# SUNNYMultiAnalyzor.net
KiCad netlist of a schematic drawn in Altium Designer
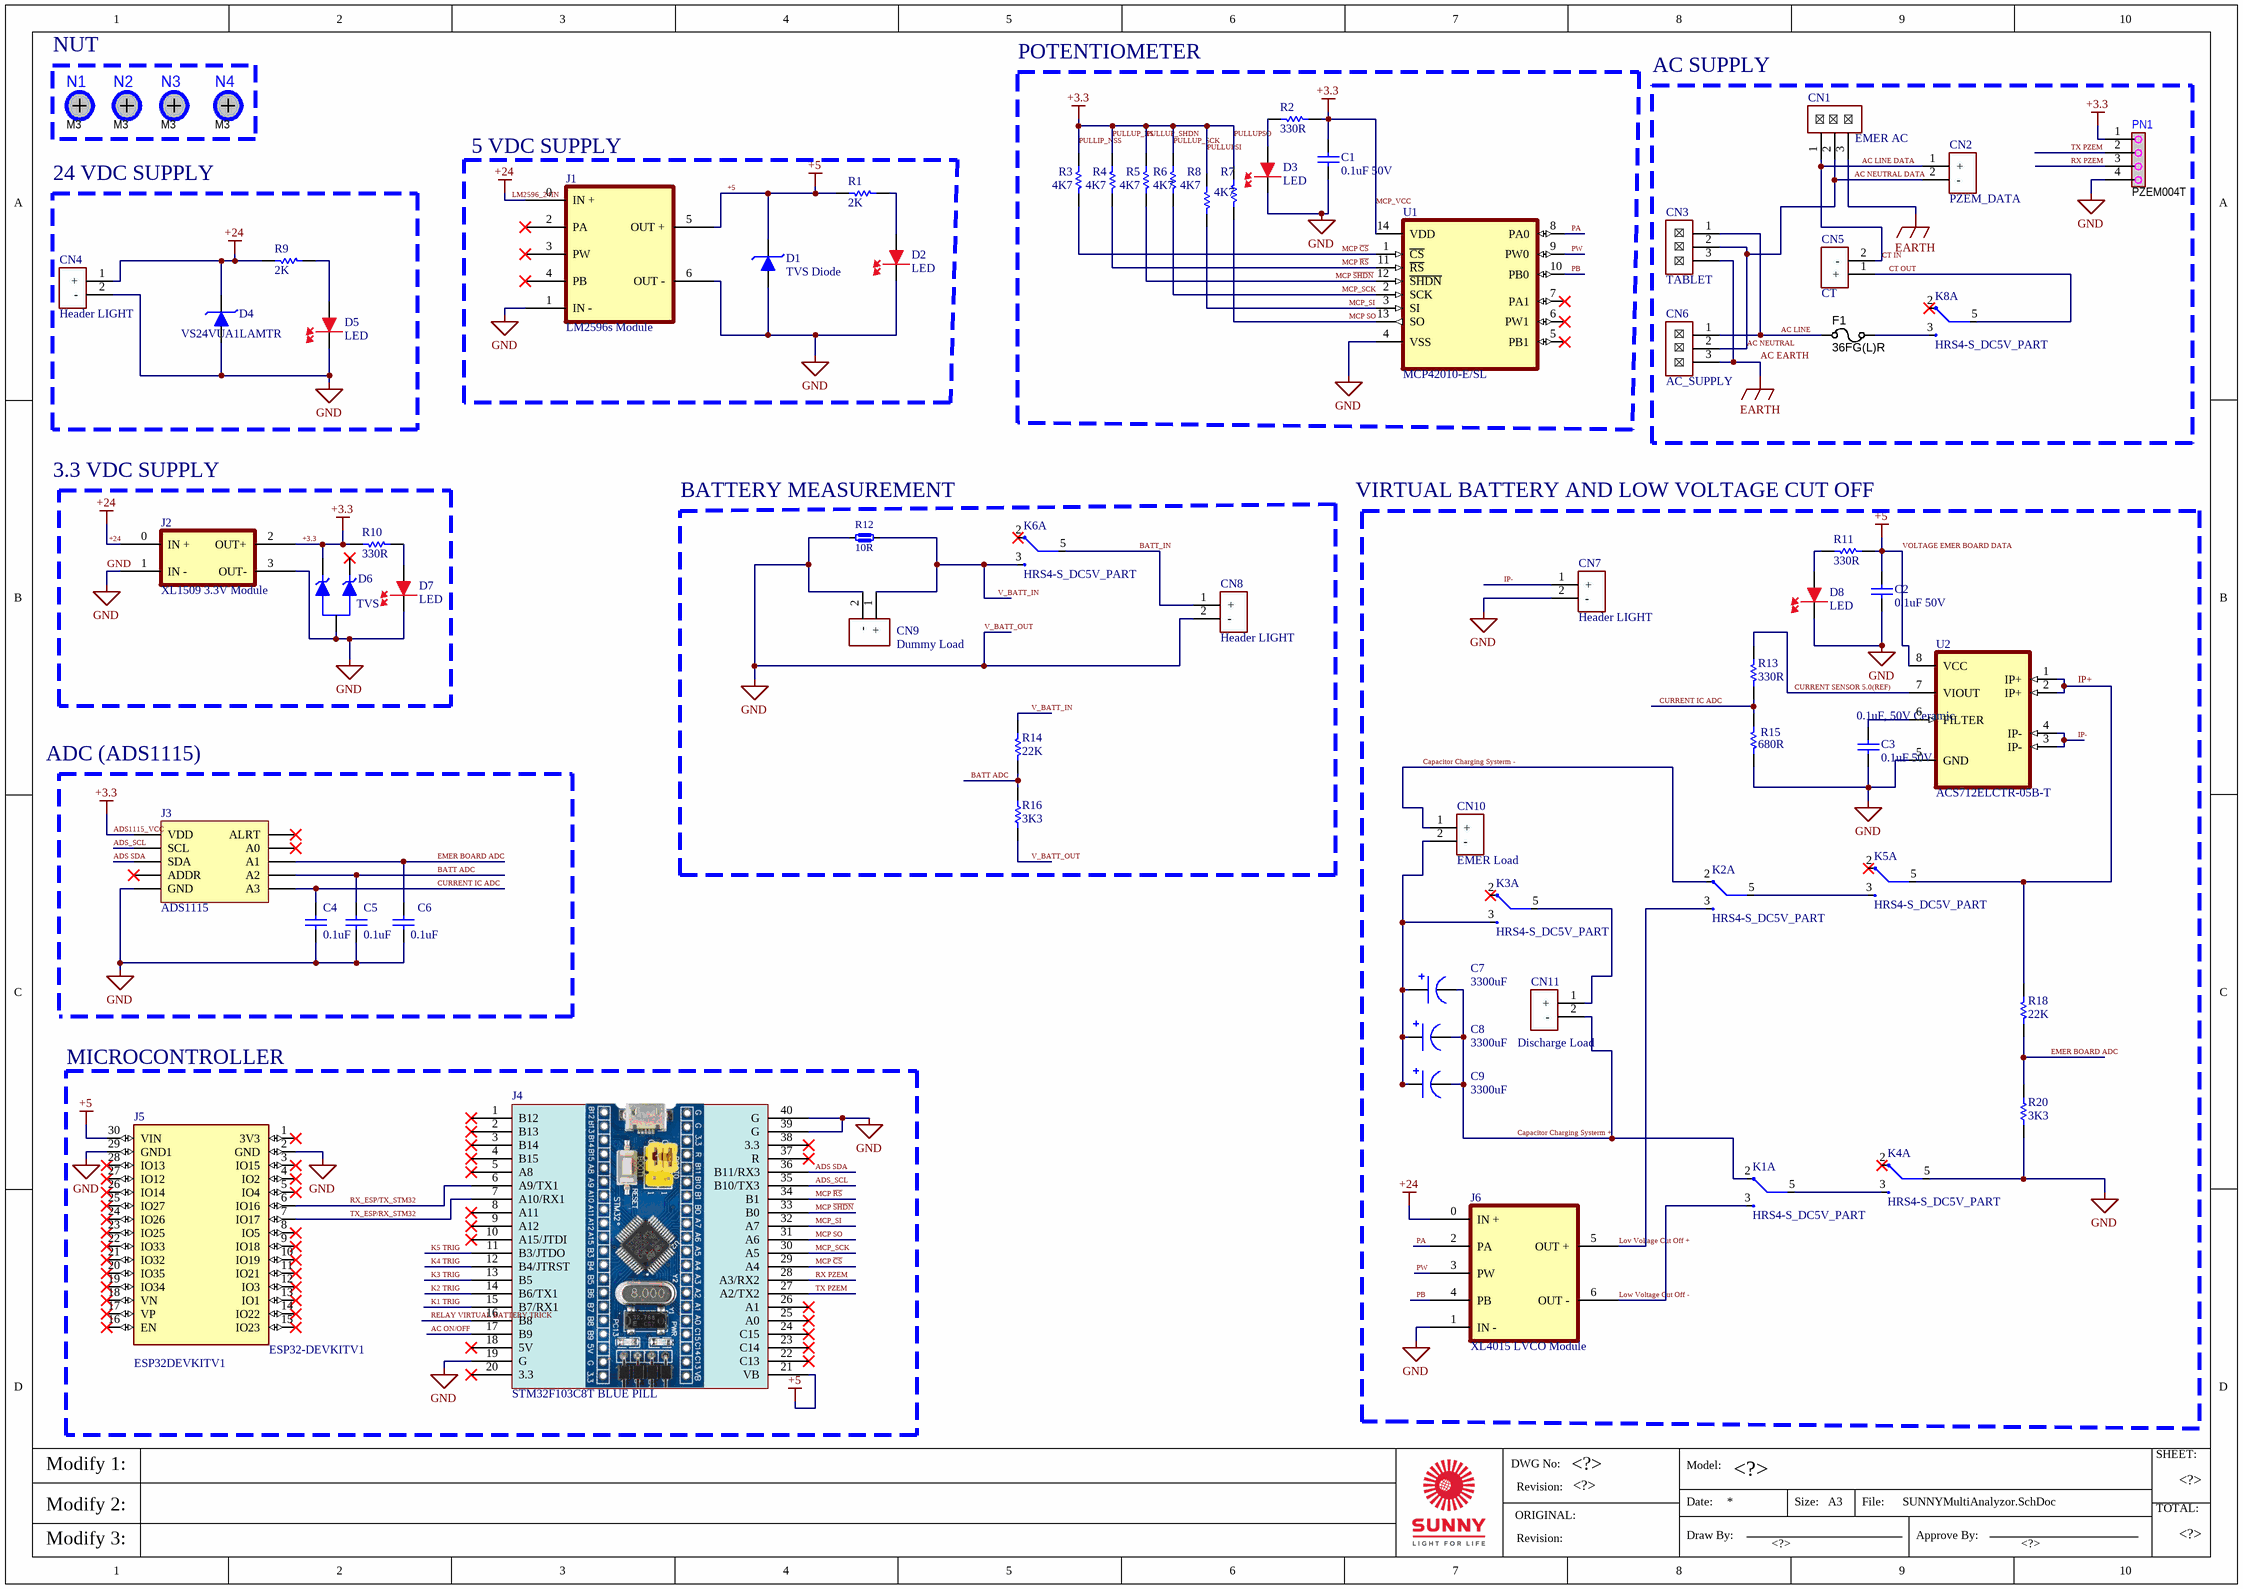
[diagram p0: SUNNYMultiAnalyzor.SchDoc]

(export (version "E")
  (design (tool "Eeschema 10.0.6"))
  (components
    (comp (ref "C1")
      (value "0.1uF 50V")
      (footprint "CAPC2012X135N")
      (description "Capacitor SMD Ceramic Chip Cap 0.1uF 50V (0805) (AVX)")
      (fields (field (name "CREATED BY") "Zion Blue") (field (name "PUBLISHER") "Cynetik Group"))
      (libsource (lib "Control INV-V21") (part "Capacitor SMD Ceramic Chip Cap 0.1uF 50V (0805) (AVX)"))
    )
    (comp (ref "C2")
      (value "0.1uF 50V")
      (footprint "CAPC2012X135N")
      (description "Capacitor SMD Ceramic Chip Cap 0.1uF 50V (0805) (AVX)")
      (fields (field (name "CREATED BY") "Zion Blue") (field (name "PUBLISHER") "Cynetik Group"))
      (libsource (lib "Control INV-V21") (part "Capacitor SMD Ceramic Chip Cap 0.1uF 50V (0805) (AVX)"))
    )
    (comp (ref "C3")
      (value "0.1uF 50V")
      (footprint "CAPC2012X135N")
      (description "Capacitor SMD Ceramic Chip Cap 0.1uF 50V (0805) (AVX)")
      (fields
        (field (name "ALTIUM_VALUE") "0.1uF, 50V Ceramic")
        (field (name "CREATED BY") "Zion Blue")
        (field (name "PUBLISHER") "Cynetik Group")
      )
      (libsource (lib "Control INV-V21") (part "Capacitor SMD Ceramic Chip Cap 0.1uF 50V (0805) (AVX)"))
    )
    (comp (ref "C4")
      (value "0.1uF")
      (footprint "CAPC2012X135N")
      (description "Capacitor SMD Ceramic Chip Cap 0.1uF 50V (0805) (AVX)")
      (fields (field (name "CREATED BY") "Zion Blue") (field (name "PUBLISHER") "Cynetik Group"))
      (libsource (lib "Control INV-V21") (part "Capacitor SMD Ceramic Chip Cap 0.1uF 50V (0805) (AVX)"))
    )
    (comp (ref "C5")
      (value "0.1uF")
      (footprint "CAPC2012X135N")
      (description "Capacitor SMD Ceramic Chip Cap 0.1uF 50V (0805) (AVX)")
      (fields (field (name "CREATED BY") "Zion Blue") (field (name "PUBLISHER") "Cynetik Group"))
      (libsource (lib "Control INV-V21") (part "Capacitor SMD Ceramic Chip Cap 0.1uF 50V (0805) (AVX)"))
    )
    (comp (ref "C6")
      (value "0.1uF")
      (footprint "CAPC2012X135N")
      (description "Capacitor SMD Ceramic Chip Cap 0.1uF 50V (0805) (AVX)")
      (fields (field (name "CREATED BY") "Zion Blue") (field (name "PUBLISHER") "Cynetik Group"))
      (libsource (lib "Control INV-V21") (part "Capacitor SMD Ceramic Chip Cap 0.1uF 50V (0805) (AVX)"))
    )
    (comp (ref "C7")
      (value "3300uF")
      (footprint "CAP3300")
      (description "3300 uF / 50 Vdc")
      (libsource (lib "PCB_Project_1") (part "Electrolytic Capacitor"))
    )
    (comp (ref "C8")
      (value "3300uF")
      (footprint "CAP3300")
      (description "3300 uF / 50 Vdc")
      (libsource (lib "PCB_Project_1") (part "Electrolytic Capacitor"))
    )
    (comp (ref "C9")
      (value "3300uF")
      (footprint "CAP3300")
      (description "3300 uF / 50 Vdc")
      (libsource (lib "PCB_Project_1") (part "Electrolytic Capacitor"))
    )
    (comp (ref "CN1")
      (value "EMER AC")
      (footprint "CON 3P 3.8mm")
      (description "Connector 3.9mm. 3PINS WAFER STRAIGHT PIN (MALE)")
      (fields (field (name "MPN") "112002ST/RH") (field (name "MANUFACTURER") "GTK"))
      (libsource (lib "MCU POWER BOARD") (part "Con 112002ST/RH 3.96mm 2P V-PLUG_1"))
    )
    (comp (ref "CN2")
      (value "PZEM_DATA")
      (footprint "Header 2 pin molex")
      (description "Connector 3.96MM 02 PIN WAFER STRAIGHTPIN (MALE)")
      (libsource (lib "MCU POWER BOARD") (part "Header LIGHT"))
    )
    (comp (ref "CN3")
      (value "TABLET")
      (footprint "CON 3P 3.8mm")
      (description "Connector 3.9mm. 3PINS WAFER STRAIGHT PIN (MALE)")
      (fields (field (name "MPN") "112002ST/RH") (field (name "MANUFACTURER") "GTK"))
      (libsource (lib "") (part "Con 112002ST/RH 3.96mm 2P V-PLUG_1_1"))
    )
    (comp (ref "CN4")
      (value "Header LIGHT")
      (footprint "HEADER 2 PIN MOLEX POLE")
      (description "Connector 3.96MM 02 PIN WAFER STRAIGHTPIN (MALE)")
      (libsource (lib "") (part "CON Header LIGHT Pole_1"))
    )
    (comp (ref "CN5")
      (value "CT")
      (footprint "Header 2 pin molex")
      (description "Connector 3.96MM 02 PIN WAFER STRAIGHTPIN (MALE)")
      (libsource (lib "") (part "Header LIGHT_2"))
    )
    (comp (ref "CN6")
      (value "AC_SUPPLY")
      (footprint "CON 3P 3.8mm")
      (description "Connector 3.9mm. 3PINS WAFER STRAIGHT PIN (MALE)")
      (fields (field (name "MPN") "112002ST/RH") (field (name "MANUFACTURER") "GTK"))
      (libsource (lib "") (part "Con 112002ST/RH 3.96mm 2P V-PLUG_1_1"))
    )
    (comp (ref "CN7")
      (value "Header LIGHT")
      (footprint "HEADER 2 PIN MOLEX POLE")
      (description "Connector 3.96MM 02 PIN WAFER STRAIGHTPIN (MALE)")
      (libsource (lib "ESP32+ATMEL") (part "CON Header LIGHT Pole"))
    )
    (comp (ref "CN8")
      (value "Header LIGHT")
      (footprint "HEADER 2 PIN MOLEX POLE")
      (description "Connector 3.96MM 02 PIN WAFER STRAIGHTPIN (MALE)")
      (libsource (lib "ESP32+ATMEL") (part "CON Header LIGHT Pole"))
    )
    (comp (ref "CN9")
      (value "Dummy Load")
      (footprint "Header 2 pin molex")
      (description "Connector 3.96MM 02 PIN WAFER STRAIGHTPIN (MALE)")
      (libsource (lib "") (part "Header LIGHT_1"))
    )
    (comp (ref "CN10")
      (value "EMER Load")
      (footprint "Header 2 pin molex")
      (description "Connector 3.96MM 02 PIN WAFER STRAIGHTPIN (MALE)")
      (libsource (lib "MCU POWER BOARD") (part "Header LIGHT"))
    )
    (comp (ref "CN11")
      (value "Discharge Load")
      (footprint "Header 2 pin molex")
      (description "Connector 3.96MM 02 PIN WAFER STRAIGHTPIN (MALE)")
      (libsource (lib "") (part "Header LIGHT_1"))
    )
    (comp (ref "D1")
      (value "TVS Diode")
      (footprint "SOD-128")
      (fields (field (name "PUBLISHER") "Altium Limited"))
      (libsource (lib "PCB_Project_1") (part "TVS Diode VS6V0UA1LAMTR"))
    )
    (comp (ref "D2")
      (value "LED")
      (footprint "0805 LED")
      (description "LED SMD  mcd,Red Color Red Diffused Lens")
      (libsource (lib "PCB_Project_1") (part "LED RED (SMD)"))
    )
    (comp (ref "D3")
      (value "LED")
      (footprint "0805 LED")
      (description "LED SMD  mcd,Red Color Red Diffused Lens")
      (libsource (lib "PCB_Project_1") (part "LED RED (SMD)"))
    )
    (comp (ref "D4")
      (value "VS24VUA1LAMTR")
      (footprint "SOD-128")
      (fields (field (name "PUBLISHER") "Altium Limited"))
      (libsource (lib "PCB_Project_1") (part "TVS Diode VS24VUA1LAMTR"))
    )
    (comp (ref "D5")
      (value "LED")
      (footprint "0805 LED")
      (description "LED SMD  mcd,Red Color Red Diffused Lens")
      (libsource (lib "PCB_Project_1") (part "LED RED (SMD)"))
    )
    (comp (ref "D6")
      (value "TVS")
      (footprint "SOT95P237X111-3N")
      (description "46V Clamp 870mA Ipp Tvs Diode Surface Mount SOT-23-3 (TO-236)")
      (fields (field (name "MP") "MMBZ6V8ALT1G"))
      (libsource (lib "PCB_Project_1") (part "TVS Diode MMBZ6V8ALT1G"))
    )
    (comp (ref "D7")
      (value "LED")
      (footprint "0805 LED")
      (description "LED SMD  mcd,Red Color Red Diffused Lens")
      (libsource (lib "PCB_Project_1") (part "LED RED (SMD)"))
    )
    (comp (ref "D8")
      (value "LED")
      (footprint "0805 LED")
      (description "LED SMD  mcd,Red Color Red Diffused Lens")
      (libsource (lib "PCB_Project_1") (part "LED RED (SMD)"))
    )
    (comp (ref "F1")
      (value "36FG(L)R")
      (footprint "Micro Fuse - L14mm")
      (description "Fuse Microfuse, 1A/250Vac, Fast Acting (Normal Blow) P/N : 36FG(L)R (SLEEK)")
      (fields (field (name "MANUFACTURER") "SLEEK") (field (name "PUBLISHER") "Cynetik Group"))
      (libsource (lib "MCU POWER BOARD") (part "Fuse 36FG(L)R 1A On pcb"))
    )
    (comp (ref "J1")
      (value "LM2596s Module")
      (footprint "LM2596s MODULE")
      (description "LM2596s Module step down converter")
      (libsource (lib "PCB_Project_1") (part "LM2596s Module 5A"))
    )
    (comp (ref "J2")
      (value "XL1509 3.3V Module")
      (footprint "XL1509 MODULE")
      (description "XL1509 Module step down converter")
      (libsource (lib "PCB_Project_1") (part "XL1509 Module"))
    )
    (comp (ref "J3")
      (value "ADS1115")
      (footprint "BNO080")
      (description "ADC Sensor")
      (fields (field (name "PUBLISHER") "Altium Limited"))
      (libsource (lib "SchlibBruno") (part "ADS1115"))
    )
    (comp (ref "J4")
      (value "STM32F103C8T BLUE PILL")
      (footprint "STM32F103 BLUE PILL")
      (description "STM32F103C8T BULE PILL")
      (libsource (lib "PCB_Project_1") (part "STM32 BULE PILL"))
    )
    (comp (ref "J5")
      (value "ESP32DEVKITV1")
      (footprint "ESP32-DEVKITV1_3D")
      (fields (field (name "MF") "Do it") (field (name "MP") "ESP32 DEVKIT V1"))
      (libsource (lib "SchlibBruno") (part "ESP32DEVKITV1"))
    )
    (comp (ref "J6")
      (value "XL4015 LVCO Module")
      (footprint "XL4015 Module")
      (description "XL4015 Module step down converter for Low Voltage Cut Off Check(LVCO)")
      (libsource (lib "PCB_Project_1") (part "XL4015 Module 5A"))
    )
    (comp (ref "K1")
      (value "HRS4-S_DC5V_PART")
      (footprint "SamacSys:HRS4SDC5V")
      (description "Relay or Contactor")
      (fields (field (name "MANUFACTURER_PART_NUMBER") "HRS4-S DC5V"))
      (libsource (lib "SamacSys") (part "HRS4-S_DC5V_PART"))
    )
    (comp (ref "K2")
      (value "HRS4-S_DC5V_PART")
      (footprint "SamacSys:HRS4SDC5V")
      (description "Relay or Contactor")
      (fields (field (name "MANUFACTURER_PART_NUMBER") "HRS4-S DC5V"))
      (libsource (lib "SamacSys") (part "HRS4-S_DC5V_PART"))
    )
    (comp (ref "K3")
      (value "HRS4-S_DC5V_PART")
      (footprint "SamacSys:HRS4SDC5V")
      (description "Relay or Contactor")
      (fields (field (name "MANUFACTURER_PART_NUMBER") "HRS4-S DC5V"))
      (libsource (lib "SamacSys") (part "HRS4-S_DC5V_PART"))
    )
    (comp (ref "K4")
      (value "HRS4-S_DC5V_PART")
      (footprint "SamacSys:HRS4SDC5V")
      (description "Relay or Contactor")
      (fields (field (name "MANUFACTURER_PART_NUMBER") "HRS4-S DC5V"))
      (libsource (lib "SamacSys") (part "HRS4-S_DC5V_PART"))
    )
    (comp (ref "K5")
      (value "HRS4-S_DC5V_PART")
      (footprint "SamacSys:HRS4SDC5V")
      (description "Relay or Contactor")
      (fields (field (name "MANUFACTURER_PART_NUMBER") "HRS4-S DC5V"))
      (libsource (lib "SamacSys") (part "HRS4-S_DC5V_PART"))
    )
    (comp (ref "K6")
      (value "HRS4-S_DC5V_PART")
      (footprint "SamacSys:HRS4SDC5V")
      (description "Relay or Contactor")
      (fields (field (name "MANUFACTURER_PART_NUMBER") "HRS4-S DC5V"))
      (libsource (lib "SamacSys") (part "HRS4-S_DC5V_PART"))
    )
    (comp (ref "K8")
      (value "HRS4-S_DC5V_PART")
      (footprint "SamacSys:HRS4SDC5V")
      (description "Relay or Contactor")
      (fields (field (name "MANUFACTURER_PART_NUMBER") "HRS4-S DC5V"))
      (libsource (lib "SamacSys") (part "HRS4-S_DC5V_PART"))
    )
    (comp (ref "N1")
      (value "M3")
      (footprint "M3 hole")
      (description "น็อต JT หัวร่ม สกรูมิลสี่แฉก M3x6")
      (libsource (lib "Control INV-V21") (part "M3 hole"))
    )
    (comp (ref "N2")
      (value "M3")
      (footprint "M3 hole")
      (description "น็อต JT หัวร่ม สกรูมิลสี่แฉก M3x6")
      (libsource (lib "Control INV-V21") (part "M3 hole"))
    )
    (comp (ref "N3")
      (value "M3")
      (footprint "M3 hole")
      (description "น็อต JT หัวร่ม สกรูมิลสี่แฉก M3x6")
      (libsource (lib "Control INV-V21") (part "M3 hole"))
    )
    (comp (ref "N4")
      (value "M3")
      (footprint "M3 hole")
      (description "น็อต JT หัวร่ม สกรูมิลสี่แฉก M3x6")
      (libsource (lib "Control INV-V21") (part "M3 hole"))
    )
    (comp (ref "PN1")
      (value "PZEM004T")
      (footprint "1x4P Test PIN")
      (description "Connector Pin Header 4 Pins,Pitch 2.54mm. P/N : PHSS04G10/RH (GTK)")
      (libsource (lib "Control INV-V21") (part "PIN Header 1X4"))
    )
    (comp (ref "R1")
      (value "2K")
      (footprint "0805 Modificado")
      (description "'RES SMD 330 OHM 5% 1/8W 0805/0805W8F3300T5E")
      (libsource (lib "MCU POWER BOARD") (part "Resistor SMD 330R +/- 1% (CHIP)"))
    )
    (comp (ref "R2")
      (value "330R")
      (footprint "0805 Modificado")
      (description "'RES SMD 330 OHM 5% 1/8W 0805/0805W8F3300T5E")
      (libsource (lib "MCU POWER BOARD") (part "Resistor SMD 330R +/- 1% (CHIP)"))
    )
    (comp (ref "R3")
      (value "4K7")
      (footprint "0805 Modificado")
      (description "'RES SMD 330 OHM 5% 1/8W 0805/0805W8F3300T5E")
      (libsource (lib "MCU POWER BOARD") (part "Resistor SMD 330R +/- 1% (CHIP)"))
    )
    (comp (ref "R4")
      (value "4K7")
      (footprint "0805 Modificado")
      (description "'RES SMD 330 OHM 5% 1/8W 0805/0805W8F3300T5E")
      (libsource (lib "MCU POWER BOARD") (part "Resistor SMD 330R +/- 1% (CHIP)"))
    )
    (comp (ref "R5")
      (value "4K7")
      (footprint "0805 Modificado")
      (description "'RES SMD 330 OHM 5% 1/8W 0805/0805W8F3300T5E")
      (libsource (lib "MCU POWER BOARD") (part "Resistor SMD 330R +/- 1% (CHIP)"))
    )
    (comp (ref "R6")
      (value "4K7")
      (footprint "0805 Modificado")
      (description "'RES SMD 330 OHM 5% 1/8W 0805/0805W8F3300T5E")
      (libsource (lib "MCU POWER BOARD") (part "Resistor SMD 330R +/- 1% (CHIP)"))
    )
    (comp (ref "R7")
      (value "4K7")
      (footprint "0805 Modificado")
      (description "'RES SMD 330 OHM 5% 1/8W 0805/0805W8F3300T5E")
      (libsource (lib "MCU POWER BOARD") (part "Resistor SMD 330R +/- 1% (CHIP)"))
    )
    (comp (ref "R8")
      (value "4K7")
      (footprint "0805 Modificado")
      (description "'RES SMD 330 OHM 5% 1/8W 0805/0805W8F3300T5E")
      (libsource (lib "MCU POWER BOARD") (part "Resistor SMD 330R +/- 1% (CHIP)"))
    )
    (comp (ref "R9")
      (value "2K")
      (footprint "0805 Modificado")
      (description "'RES SMD 330 OHM 5% 1/8W 0805/0805W8F3300T5E")
      (libsource (lib "MCU POWER BOARD") (part "Resistor SMD 330R +/- 1% (CHIP)"))
    )
    (comp (ref "R10")
      (value "330R")
      (footprint "0805 Modificado")
      (description "'RES SMD 330 OHM 5% 1/8W 0805/0805W8F3300T5E")
      (libsource (lib "MCU POWER BOARD") (part "Resistor SMD 330R +/- 1% (CHIP)"))
    )
    (comp (ref "R11")
      (value "330R")
      (footprint "0805 Modificado")
      (description "'RES SMD 330 OHM 5% 1/8W 0805/0805W8F3300T5E")
      (libsource (lib "MCU POWER BOARD") (part "Resistor SMD 330R +/- 1% (CHIP)"))
    )
    (comp (ref "R12")
      (value "10R")
      (description "10 OHM , 40 W . Made by Parallel of 2 Resistor 20 OHM 20 W")
      (libsource (lib "PCB_Project_1") (part "Dummy Load"))
    )
    (comp (ref "R13")
      (value "330R")
      (footprint "0805 Modificado")
      (description "'RES SMD 330 OHM 5% 1/8W 0805/0805W8F3300T5E")
      (libsource (lib "MCU POWER BOARD") (part "Resistor SMD 330R +/- 1% (CHIP)"))
    )
    (comp (ref "R14")
      (value "22K")
      (footprint "0805 Modificado")
      (description "'RES SMD 330 OHM 5% 1/8W 0805/0805W8F3300T5E")
      (libsource (lib "MCU POWER BOARD") (part "Resistor SMD 330R +/- 1% (CHIP)"))
    )
    (comp (ref "R15")
      (value "680R")
      (footprint "0603 RESISTOR")
      (description "'RES SMD 330 OHM 5% 1/8W 0805/0805W8F3300T5E")
      (libsource (lib "MCU POWER BOARD") (part "Resistor SMD 330R +/- 1% (CHIP)"))
    )
    (comp (ref "R16")
      (value "3K3")
      (footprint "1206 RESISTOR")
      (description "'RES SMD 330 OHM 5% 1/8W 0805/0805W8F3300T5E")
      (libsource (lib "MCU POWER BOARD") (part "Resistor SMD 330R +/- 1% (CHIP)"))
    )
    (comp (ref "R18")
      (value "22K")
      (footprint "0805 Modificado")
      (description "'RES SMD 330 OHM 5% 1/8W 0805/0805W8F3300T5E")
      (libsource (lib "MCU POWER BOARD") (part "Resistor SMD 330R +/- 1% (CHIP)"))
    )
    (comp (ref "R20")
      (value "3K3")
      (footprint "1206 RESISTOR")
      (description "'RES SMD 330 OHM 5% 1/8W 0805/0805W8F3300T5E")
      (libsource (lib "MCU POWER BOARD") (part "Resistor SMD 330R +/- 1% (CHIP)"))
    )
    (comp (ref "U1")
      (value "MCP42010-E/SL")
      (footprint "SOIC127P600X175-14N")
      (description "Digital Potentiometer 10k Ohm 2 Circuit 256 Taps SPI Interface 14-SOIC")
      (fields (field (name "MF") "Microchip"))
      (libsource (lib "PCB_Project_1") (part "MCP42010-E/SL"))
    )
    (comp (ref "U2")
      (value "ACS712ELCTR-05B-T")
      (footprint "SOIC127P600X175-8N")
      (description "Current Sensor 5A 1 Channel Hall Effect, Open Loop Bidirectional 8-SOIC (0.154, 3.90mm Width)")
      (fields (field (name "MF") "Allegro MicroSystems LLC"))
      (libsource (lib "ACS712ELCTR-05B-T") (part "ACS712ELCTR-05B-T"))
    )
  )
  (nets
    (net (code "1") (name "+3.3") (class "Default")
      (node (ref "C1") (pin "2") (pinfunction "2_2") (pintype "passive"))
      (node (ref "D6") (pin "2") (pinfunction "K2_2") (pintype "passive"))
      (node (ref "J2") (pin "2") (pinfunction "OUT+_2") (pintype "passive"))
      (node (ref "J3") (pin "1") (pinfunction "VDD_1") (pintype "passive"))
      (node (ref "PN1") (pin "1") (pinfunction "1_1") (pintype "passive"))
      (node (ref "R10") (pin "2") (pinfunction "2_2") (pintype "passive"))
      (node (ref "R2") (pin "1") (pinfunction "1_1") (pintype "passive"))
      (node (ref "R3") (pin "1") (pinfunction "1_1") (pintype "passive"))
      (node (ref "R4") (pin "1") (pinfunction "1_1") (pintype "passive"))
      (node (ref "R5") (pin "1") (pinfunction "1_1") (pintype "passive"))
      (node (ref "R6") (pin "1") (pinfunction "1_1") (pintype "passive"))
      (node (ref "R7") (pin "1") (pinfunction "1_1") (pintype "passive"))
      (node (ref "R8") (pin "1") (pinfunction "1_1") (pintype "passive"))
      (node (ref "U1") (pin "14") (pinfunction "VDD_14") (pintype "power_in"))
    )
    (net (code "2") (name "+5") (class "Default")
      (node (ref "C2") (pin "2") (pinfunction "2_2") (pintype "passive"))
      (node (ref "D1") (pin "2") (pinfunction "K_2") (pintype "passive"))
      (node (ref "J1") (pin "5") (pinfunction "OUT_+_5") (pintype "passive"))
      (node (ref "J4") (pin "21") (pinfunction "VB_21") (pintype "passive"))
      (node (ref "J5") (pin "30") (pinfunction "VIN_30") (pintype "bidirectional"))
      (node (ref "R1") (pin "2") (pinfunction "2_2") (pintype "passive"))
      (node (ref "R11") (pin "1") (pinfunction "1_1") (pintype "passive"))
      (node (ref "U2") (pin "8") (pinfunction "VCC_8") (pintype "passive"))
    )
    (net (code "3") (name "+24") (class "Default")
      (node (ref "CN4") (pin "1") (pinfunction "+_1") (pintype "passive"))
      (node (ref "D4") (pin "2") (pinfunction "K_2") (pintype "passive"))
      (node (ref "J1") (pin "0") (pinfunction "IN_+_0") (pintype "passive"))
      (node (ref "J2") (pin "0") (pinfunction "IN_+_0") (pintype "passive"))
      (node (ref "J6") (pin "0") (pinfunction "IN_+_0") (pintype "passive"))
      (node (ref "R9") (pin "2") (pinfunction "2_2") (pintype "passive"))
    )
    (net (code "4") (name "/AC LINE") (class "Default")
      (node (ref "CN3") (pin "1") (pinfunction "1_1") (pintype "passive"))
      (node (ref "CN6") (pin "1") (pinfunction "1_1") (pintype "passive"))
      (node (ref "F1") (pin "1") (pinfunction "1_1") (pintype "passive"))
    )
    (net (code "5") (name "/AC LINE DATA") (class "Default")
      (node (ref "CN1") (pin "1") (pinfunction "1_1") (pintype "passive"))
      (node (ref "CN2") (pin "1") (pinfunction "+_1") (pintype "passive"))
      (node (ref "CN5") (pin "2") (pinfunction "-_2") (pintype "passive"))
    )
    (net (code "6") (name "/AC NEUTRAL") (class "Default")
      (node (ref "CN1") (pin "2") (pinfunction "2_2") (pintype "passive"))
      (node (ref "CN2") (pin "2") (pinfunction "-_2") (pintype "passive"))
      (node (ref "CN3") (pin "2") (pinfunction "2_2") (pintype "passive"))
      (node (ref "CN6") (pin "2") (pinfunction "2_2") (pintype "passive"))
    )
    (net (code "7") (name "/AC ON{slash}OFF") (class "Default")
      (node (ref "J4") (pin "17") (pinfunction "B9_17") (pintype "passive"))
    )
    (net (code "8") (name "/ADS SDA") (class "Default")
      (node (ref "J3") (pin "4") (pinfunction "SDA_4") (pintype "passive"))
      (node (ref "J4") (pin "36") (pinfunction "B11/RX3_36") (pintype "passive"))
    )
    (net (code "9") (name "/ADS_SCL") (class "Default")
      (node (ref "J3") (pin "3") (pinfunction "SCL_3") (pintype "passive"))
      (node (ref "J4") (pin "35") (pinfunction "B10/TX3_35") (pintype "passive"))
    )
    (net (code "10") (name "/BATT ADC") (class "Default")
      (node (ref "C5") (pin "2") (pinfunction "2_2") (pintype "passive"))
      (node (ref "J3") (pin "9") (pinfunction "A2_9") (pintype "passive"))
      (node (ref "R14") (pin "1") (pinfunction "1_1") (pintype "passive"))
      (node (ref "R16") (pin "2") (pinfunction "2_2") (pintype "passive"))
    )
    (net (code "11") (name "/BATT_IN") (class "Default")
      (node (ref "CN8") (pin "1") (pinfunction "+_1") (pintype "passive"))
      (node (ref "K6") (pin "5") (pinfunction "COM_5") (pintype "passive"))
    )
    (net (code "12") (name "/CT OUT") (class "Default")
      (node (ref "CN5") (pin "1") (pinfunction "+_1") (pintype "passive"))
      (node (ref "K8") (pin "5") (pinfunction "COM_5") (pintype "passive"))
    )
    (net (code "13") (name "/CURRENT IC ADC") (class "Default")
      (node (ref "C4") (pin "2") (pinfunction "2_2") (pintype "passive"))
      (node (ref "J3") (pin "10") (pinfunction "A3_10") (pintype "passive"))
      (node (ref "R13") (pin "2") (pinfunction "2_2") (pintype "passive"))
      (node (ref "R15") (pin "1") (pinfunction "1_1") (pintype "passive"))
    )
    (net (code "14") (name "/CURRENT SENSOR 5.0(REF)") (class "Default")
      (node (ref "R13") (pin "1") (pinfunction "1_1") (pintype "passive"))
      (node (ref "U2") (pin "7") (pinfunction "VIOUT_7") (pintype "passive"))
    )
    (net (code "15") (name "/Capacitor Charging Systerm +") (class "Default")
      (node (ref "C7") (pin "N") (pinfunction "1_N") (pintype "passive"))
      (node (ref "C8") (pin "N") (pinfunction "1_N") (pintype "passive"))
      (node (ref "C9") (pin "N") (pinfunction "1_N") (pintype "passive"))
      (node (ref "CN11") (pin "2") (pinfunction "-_2") (pintype "passive"))
      (node (ref "K1") (pin "2") (pinfunction "NC_2") (pintype "passive"))
    )
    (net (code "16") (name "/Capacitor Charging Systerm -") (class "Default")
      (node (ref "CN10") (pin "1") (pinfunction "+_1") (pintype "passive"))
      (node (ref "K2") (pin "2") (pinfunction "NC_2") (pintype "passive"))
    )
    (net (code "17") (name "/EMER BOARD ADC") (class "Default")
      (node (ref "C6") (pin "2") (pinfunction "2_2") (pintype "passive"))
      (node (ref "J3") (pin "8") (pinfunction "A1_8") (pintype "passive"))
      (node (ref "R18") (pin "2") (pinfunction "2_2") (pintype "passive"))
      (node (ref "R20") (pin "1") (pinfunction "1_1") (pintype "passive"))
    )
    (net (code "18") (name "/IP+") (class "Default")
      (node (ref "K5") (pin "5") (pinfunction "COM_5") (pintype "passive"))
      (node (ref "R18") (pin "1") (pinfunction "1_1") (pintype "passive"))
      (node (ref "U2") (pin "1") (pinfunction "IP+_1") (pintype "input"))
      (node (ref "U2") (pin "2") (pinfunction "IP+_2") (pintype "input"))
    )
    (net (code "19") (name "/IP-") (class "Default")
      (node (ref "CN7") (pin "1") (pinfunction "+_1") (pintype "passive"))
      (node (ref "U2") (pin "3") (pinfunction "IP-_3") (pintype "input"))
      (node (ref "U2") (pin "4") (pinfunction "IP-_4") (pintype "input"))
    )
    (net (code "20") (name "/K1 TRIG") (class "Default")
      (node (ref "J4") (pin "15") (pinfunction "B7/RX1_15") (pintype "passive"))
    )
    (net (code "21") (name "/K2 TRIG") (class "Default")
      (node (ref "J4") (pin "14") (pinfunction "B6/TX1_14") (pintype "passive"))
    )
    (net (code "22") (name "/K3 TRIG") (class "Default")
      (node (ref "J4") (pin "13") (pinfunction "B5_13") (pintype "passive"))
    )
    (net (code "23") (name "/K4 TRIG") (class "Default")
      (node (ref "J4") (pin "12") (pinfunction "B4/JTRST_12") (pintype "passive"))
    )
    (net (code "24") (name "/K5 TRIG") (class "Default")
      (node (ref "J4") (pin "11") (pinfunction "B3/JTDO_11") (pintype "passive"))
    )
    (net (code "25") (name "/Lov Voltage Cut Off +") (class "Default")
      (node (ref "J6") (pin "5") (pinfunction "OUT_+_5") (pintype "passive"))
      (node (ref "K2") (pin "3") (pinfunction "NO_3") (pintype "passive"))
    )
    (net (code "26") (name "/Low Voltage Cut Off -") (class "Default")
      (node (ref "J6") (pin "6") (pinfunction "OUT_-_6") (pintype "passive"))
      (node (ref "K1") (pin "3") (pinfunction "NO_3") (pintype "passive"))
    )
    (net (code "27") (name "/MCP SO") (class "Default")
      (node (ref "J4") (pin "31") (pinfunction "A6_31") (pintype "passive"))
      (node (ref "R7") (pin "2") (pinfunction "2_2") (pintype "passive"))
      (node (ref "U1") (pin "13") (pinfunction "SO_13") (pintype "output"))
    )
    (net (code "28") (name "/MCP ~{CS}") (class "Default")
      (node (ref "J4") (pin "29") (pinfunction "A4_29") (pintype "passive"))
      (node (ref "R3") (pin "2") (pinfunction "2_2") (pintype "passive"))
      (node (ref "U1") (pin "1") (pinfunction "~{CS}_1") (pintype "input"))
    )
    (net (code "29") (name "/MCP ~{RS}") (class "Default")
      (node (ref "J4") (pin "34") (pinfunction "B1_34") (pintype "passive"))
      (node (ref "R4") (pin "2") (pinfunction "2_2") (pintype "passive"))
      (node (ref "U1") (pin "11") (pinfunction "~{RS}_11") (pintype "input"))
    )
    (net (code "30") (name "/MCP ~{SHDN}") (class "Default")
      (node (ref "J4") (pin "33") (pinfunction "B0_33") (pintype "passive"))
      (node (ref "R5") (pin "2") (pinfunction "2_2") (pintype "passive"))
      (node (ref "U1") (pin "12") (pinfunction "~{SHDN}_12") (pintype "input"))
    )
    (net (code "31") (name "/MCP_SCK") (class "Default")
      (node (ref "J4") (pin "30") (pinfunction "A5_30") (pintype "passive"))
      (node (ref "R6") (pin "2") (pinfunction "2_2") (pintype "passive"))
      (node (ref "U1") (pin "2") (pinfunction "SCK_2") (pintype "input"))
    )
    (net (code "32") (name "/MCP_SI") (class "Default")
      (node (ref "J4") (pin "32") (pinfunction "A7_32") (pintype "passive"))
      (node (ref "R8") (pin "2") (pinfunction "2_2") (pintype "passive"))
      (node (ref "U1") (pin "3") (pinfunction "SI_3") (pintype "input"))
    )
    (net (code "33") (name "/PA") (class "Default")
      (node (ref "J6") (pin "2") (pinfunction "PA_2") (pintype "passive"))
      (node (ref "U1") (pin "8") (pinfunction "PA0_8") (pintype "bidirectional"))
    )
    (net (code "34") (name "/PB") (class "Default")
      (node (ref "J6") (pin "4") (pinfunction "PB_4") (pintype "passive"))
      (node (ref "U1") (pin "10") (pinfunction "PB0_10") (pintype "bidirectional"))
    )
    (net (code "35") (name "/PW") (class "Default")
      (node (ref "J6") (pin "3") (pinfunction "PW_3") (pintype "passive"))
      (node (ref "U1") (pin "9") (pinfunction "PW0_9") (pintype "bidirectional"))
    )
    (net (code "36") (name "/RELAY VIRTUAL BATTERY TRICK") (class "Default")
      (node (ref "J4") (pin "16") (pinfunction "B8_16") (pintype "passive"))
    )
    (net (code "37") (name "/RX PZEM") (class "Default")
      (node (ref "J4") (pin "28") (pinfunction "A3/RX2_28") (pintype "passive"))
      (node (ref "PN1") (pin "3") (pinfunction "3_3") (pintype "passive"))
    )
    (net (code "38") (name "/RX_ESP{slash}TX_STM32") (class "Default")
      (node (ref "J4") (pin "6") (pinfunction "A9/TX1_6") (pintype "passive"))
      (node (ref "J5") (pin "6") (pinfunction "IO16_6") (pintype "bidirectional"))
    )
    (net (code "39") (name "/TX PZEM") (class "Default")
      (node (ref "J4") (pin "27") (pinfunction "A2/TX2_27") (pintype "passive"))
      (node (ref "PN1") (pin "2") (pinfunction "2_2") (pintype "passive"))
    )
    (net (code "40") (name "/TX_ESP{slash}RX_STM32") (class "Default")
      (node (ref "J4") (pin "7") (pinfunction "A10/RX1_7") (pintype "passive"))
      (node (ref "J5") (pin "7") (pinfunction "IO17_7") (pintype "bidirectional"))
    )
    (net (code "41") (name "/V_BATT_IN") (class "Default")
      (node (ref "CN9") (pin "1") (pinfunction "+_1") (pintype "passive"))
      (node (ref "K6") (pin "3") (pinfunction "NO_3") (pintype "passive"))
      (node (ref "R12") (pin "2") (pinfunction "2_2") (pintype "passive"))
      (node (ref "R14") (pin "2") (pinfunction "2_2") (pintype "passive"))
    )
    (net (code "42") (name "EARTH") (class "Default")
      (node (ref "CN1") (pin "3") (pinfunction "3_3") (pintype "passive"))
      (node (ref "CN3") (pin "3") (pinfunction "3_3") (pintype "passive"))
      (node (ref "CN6") (pin "3") (pinfunction "3_3") (pintype "passive"))
    )
    (net (code "43") (name "GND") (class "Default")
      (node (ref "C1") (pin "1") (pinfunction "1_1") (pintype "passive"))
      (node (ref "C2") (pin "1") (pinfunction "1_1") (pintype "passive"))
      (node (ref "C3") (pin "1") (pinfunction "1_1") (pintype "passive"))
      (node (ref "C4") (pin "1") (pinfunction "1_1") (pintype "passive"))
      (node (ref "C5") (pin "1") (pinfunction "1_1") (pintype "passive"))
      (node (ref "C6") (pin "1") (pinfunction "1_1") (pintype "passive"))
      (node (ref "CN4") (pin "2") (pinfunction "-_2") (pintype "passive"))
      (node (ref "CN7") (pin "2") (pinfunction "-_2") (pintype "passive"))
      (node (ref "CN8") (pin "2") (pinfunction "-_2") (pintype "passive"))
      (node (ref "CN9") (pin "2") (pinfunction "-_2") (pintype "passive"))
      (node (ref "D1") (pin "1") (pinfunction "A_1") (pintype "passive"))
      (node (ref "D2") (pin "1") (pinfunction "K_1") (pintype "passive"))
      (node (ref "D3") (pin "1") (pinfunction "K_1") (pintype "passive"))
      (node (ref "D4") (pin "1") (pinfunction "A_1") (pintype "passive"))
      (node (ref "D5") (pin "1") (pinfunction "K_1") (pintype "passive"))
      (node (ref "D6") (pin "3") (pinfunction "A_3") (pintype "passive"))
      (node (ref "D7") (pin "1") (pinfunction "K_1") (pintype "passive"))
      (node (ref "D8") (pin "1") (pinfunction "K_1") (pintype "passive"))
      (node (ref "J1") (pin "1") (pinfunction "IN_-_1") (pintype "passive"))
      (node (ref "J1") (pin "6") (pinfunction "OUT_-_6") (pintype "passive"))
      (node (ref "J2") (pin "1") (pinfunction "IN_-_1") (pintype "passive"))
      (node (ref "J2") (pin "3") (pinfunction "OUT-_3") (pintype "passive"))
      (node (ref "J3") (pin "2") (pinfunction "GND_2") (pintype "passive"))
      (node (ref "J4") (pin "19") (pinfunction "G_19") (pintype "passive"))
      (node (ref "J4") (pin "39") (pinfunction "G_39") (pintype "passive"))
      (node (ref "J4") (pin "40") (pinfunction "G_40") (pintype "passive"))
      (node (ref "J5") (pin "2") (pinfunction "GND_2") (pintype "bidirectional"))
      (node (ref "J5") (pin "29") (pinfunction "GND1_29") (pintype "bidirectional"))
      (node (ref "J6") (pin "1") (pinfunction "IN_-_1") (pintype "passive"))
      (node (ref "K4") (pin "5") (pinfunction "COM_5") (pintype "passive"))
      (node (ref "PN1") (pin "4") (pinfunction "4_4") (pintype "passive"))
      (node (ref "R12") (pin "1") (pinfunction "1_1") (pintype "passive"))
      (node (ref "R15") (pin "2") (pinfunction "2_2") (pintype "passive"))
      (node (ref "R16") (pin "1") (pinfunction "1_1") (pintype "passive"))
      (node (ref "R20") (pin "2") (pinfunction "2_2") (pintype "passive"))
      (node (ref "U1") (pin "4") (pinfunction "VSS_4") (pintype "passive"))
      (node (ref "U2") (pin "5") (pinfunction "GND_5") (pintype "passive"))
    )
    (net (code "44") (name "Net-(C7-0)") (class "Default")
      (node (ref "C7") (pin "P") (pinfunction "0_P") (pintype "passive"))
      (node (ref "C8") (pin "P") (pinfunction "0_P") (pintype "passive"))
      (node (ref "C9") (pin "P") (pinfunction "0_P") (pintype "passive"))
      (node (ref "CN10") (pin "2") (pinfunction "-_2") (pintype "passive"))
      (node (ref "K3") (pin "3") (pinfunction "NO_3") (pintype "passive"))
    )
    (net (code "45") (name "Net-(CN11-+)") (class "Default")
      (node (ref "CN11") (pin "1") (pinfunction "+_1") (pintype "passive"))
      (node (ref "K3") (pin "5") (pinfunction "COM_5") (pintype "passive"))
    )
    (net (code "46") (name "Net-(D2-A)") (class "Default")
      (node (ref "D2") (pin "2") (pinfunction "A_2") (pintype "passive"))
      (node (ref "R1") (pin "1") (pinfunction "1_1") (pintype "passive"))
    )
    (net (code "47") (name "Net-(D3-A)") (class "Default")
      (node (ref "D3") (pin "2") (pinfunction "A_2") (pintype "passive"))
      (node (ref "R2") (pin "2") (pinfunction "2_2") (pintype "passive"))
    )
    (net (code "48") (name "Net-(D5-A)") (class "Default")
      (node (ref "D5") (pin "2") (pinfunction "A_2") (pintype "passive"))
      (node (ref "R9") (pin "1") (pinfunction "1_1") (pintype "passive"))
    )
    (net (code "49") (name "Net-(D7-A)") (class "Default")
      (node (ref "D7") (pin "2") (pinfunction "A_2") (pintype "passive"))
      (node (ref "R10") (pin "1") (pinfunction "1_1") (pintype "passive"))
    )
    (net (code "50") (name "Net-(D8-A)") (class "Default")
      (node (ref "D8") (pin "2") (pinfunction "A_2") (pintype "passive"))
      (node (ref "R11") (pin "2") (pinfunction "2_2") (pintype "passive"))
    )
    (net (code "51") (name "Net-(K1A-COM)") (class "Default")
      (node (ref "K1") (pin "5") (pinfunction "COM_5") (pintype "passive"))
      (node (ref "K4") (pin "3") (pinfunction "NO_3") (pintype "passive"))
    )
    (net (code "52") (name "Net-(K2A-COM)") (class "Default")
      (node (ref "K2") (pin "5") (pinfunction "COM_5") (pintype "passive"))
      (node (ref "K5") (pin "3") (pinfunction "NO_3") (pintype "passive"))
    )
    (net (code "53") (name "Net-(K8A-NO)") (class "Default")
      (node (ref "F1") (pin "2") (pinfunction "2_2") (pintype "passive"))
      (node (ref "K8") (pin "3") (pinfunction "NO_3") (pintype "passive"))
    )
    (net (code "54") (name "Net-(U2-FILTER)") (class "Default")
      (node (ref "C3") (pin "2") (pinfunction "2_2") (pintype "passive"))
      (node (ref "U2") (pin "6") (pinfunction "FILTER_6") (pintype "input"))
    )
    (net (code "55") (name "unconnected-(D6-K1-Pad1)") (class "Default")
      (node (ref "D6") (pin "1") (pinfunction "K1_1") (pintype "passive+no_connect"))
    )
    (net (code "56") (name "unconnected-(J1-PA-Pad2)") (class "Default")
      (node (ref "J1") (pin "2") (pinfunction "PA_2") (pintype "passive+no_connect"))
    )
    (net (code "57") (name "unconnected-(J1-PB-Pad4)") (class "Default")
      (node (ref "J1") (pin "4") (pinfunction "PB_4") (pintype "passive+no_connect"))
    )
    (net (code "58") (name "unconnected-(J1-PW-Pad3)") (class "Default")
      (node (ref "J1") (pin "3") (pinfunction "PW_3") (pintype "passive+no_connect"))
    )
    (net (code "59") (name "unconnected-(J3-A0-Pad7)") (class "Default")
      (node (ref "J3") (pin "7") (pinfunction "A0_7") (pintype "passive+no_connect"))
    )
    (net (code "60") (name "unconnected-(J3-ADDR-Pad5)") (class "Default")
      (node (ref "J3") (pin "5") (pinfunction "ADDR_5") (pintype "passive+no_connect"))
    )
    (net (code "61") (name "unconnected-(J3-ALRT-Pad6)") (class "Default")
      (node (ref "J3") (pin "6") (pinfunction "ALRT_6") (pintype "passive+no_connect"))
    )
    (net (code "62") (name "unconnected-(J4-3.3-Pad20)") (class "Default")
      (node (ref "J4") (pin "20") (pinfunction "3.3_20") (pintype "passive+no_connect"))
    )
    (net (code "63") (name "unconnected-(J4-3.3-Pad38)") (class "Default")
      (node (ref "J4") (pin "38") (pinfunction "3.3_38") (pintype "passive+no_connect"))
    )
    (net (code "64") (name "unconnected-(J4-5V-Pad18)") (class "Default")
      (node (ref "J4") (pin "18") (pinfunction "5V_18") (pintype "passive+no_connect"))
    )
    (net (code "65") (name "unconnected-(J4-A0-Pad25)") (class "Default")
      (node (ref "J4") (pin "25") (pinfunction "A0_25") (pintype "passive+no_connect"))
    )
    (net (code "66") (name "unconnected-(J4-A1-Pad26)") (class "Default")
      (node (ref "J4") (pin "26") (pinfunction "A1_26") (pintype "passive+no_connect"))
    )
    (net (code "67") (name "unconnected-(J4-A8-Pad5)") (class "Default")
      (node (ref "J4") (pin "5") (pinfunction "A8_5") (pintype "passive+no_connect"))
    )
    (net (code "68") (name "unconnected-(J4-A11-Pad8)") (class "Default")
      (node (ref "J4") (pin "8") (pinfunction "A11_8") (pintype "passive+no_connect"))
    )
    (net (code "69") (name "unconnected-(J4-A12-Pad9)") (class "Default")
      (node (ref "J4") (pin "9") (pinfunction "A12_9") (pintype "passive+no_connect"))
    )
    (net (code "70") (name "unconnected-(J4-A15{slash}JTDI-Pad10)") (class "Default")
      (node (ref "J4") (pin "10") (pinfunction "A15/JTDI_10") (pintype "passive+no_connect"))
    )
    (net (code "71") (name "unconnected-(J4-B12-Pad1)") (class "Default")
      (node (ref "J4") (pin "1") (pinfunction "B12_1") (pintype "passive+no_connect"))
    )
    (net (code "72") (name "unconnected-(J4-B13-Pad2)") (class "Default")
      (node (ref "J4") (pin "2") (pinfunction "B13_2") (pintype "passive+no_connect"))
    )
    (net (code "73") (name "unconnected-(J4-B14-Pad3)") (class "Default")
      (node (ref "J4") (pin "3") (pinfunction "B14_3") (pintype "passive+no_connect"))
    )
    (net (code "74") (name "unconnected-(J4-B15-Pad4)") (class "Default")
      (node (ref "J4") (pin "4") (pinfunction "B15_4") (pintype "passive+no_connect"))
    )
    (net (code "75") (name "unconnected-(J4-C13-Pad22)") (class "Default")
      (node (ref "J4") (pin "22") (pinfunction "C13_22") (pintype "passive+no_connect"))
    )
    (net (code "76") (name "unconnected-(J4-C14-Pad23)") (class "Default")
      (node (ref "J4") (pin "23") (pinfunction "C14_23") (pintype "passive+no_connect"))
    )
    (net (code "77") (name "unconnected-(J4-C15-Pad24)") (class "Default")
      (node (ref "J4") (pin "24") (pinfunction "C15_24") (pintype "passive+no_connect"))
    )
    (net (code "78") (name "unconnected-(J4-R-Pad37)") (class "Default")
      (node (ref "J4") (pin "37") (pinfunction "R_37") (pintype "passive+no_connect"))
    )
    (net (code "79") (name "unconnected-(J5-3V3-Pad1)") (class "Default")
      (node (ref "J5") (pin "1") (pinfunction "3V3_1") (pintype "bidirectional+no_connect"))
    )
    (net (code "80") (name "unconnected-(J5-EN-Pad16)") (class "Default")
      (node (ref "J5") (pin "16") (pinfunction "EN_16") (pintype "bidirectional+no_connect"))
    )
    (net (code "81") (name "unconnected-(J5-IO1-Pad13)") (class "Default")
      (node (ref "J5") (pin "13") (pinfunction "IO1_13") (pintype "bidirectional+no_connect"))
    )
    (net (code "82") (name "unconnected-(J5-IO2-Pad4)") (class "Default")
      (node (ref "J5") (pin "4") (pinfunction "IO2_4") (pintype "bidirectional+no_connect"))
    )
    (net (code "83") (name "unconnected-(J5-IO3-Pad12)") (class "Default")
      (node (ref "J5") (pin "12") (pinfunction "IO3_12") (pintype "bidirectional+no_connect"))
    )
    (net (code "84") (name "unconnected-(J5-IO4-Pad5)") (class "Default")
      (node (ref "J5") (pin "5") (pinfunction "IO4_5") (pintype "bidirectional+no_connect"))
    )
    (net (code "85") (name "unconnected-(J5-IO5-Pad8)") (class "Default")
      (node (ref "J5") (pin "8") (pinfunction "IO5_8") (pintype "bidirectional+no_connect"))
    )
    (net (code "86") (name "unconnected-(J5-IO12-Pad27)") (class "Default")
      (node (ref "J5") (pin "27") (pinfunction "IO12_27") (pintype "bidirectional+no_connect"))
    )
    (net (code "87") (name "unconnected-(J5-IO13-Pad28)") (class "Default")
      (node (ref "J5") (pin "28") (pinfunction "IO13_28") (pintype "bidirectional+no_connect"))
    )
    (net (code "88") (name "unconnected-(J5-IO14-Pad26)") (class "Default")
      (node (ref "J5") (pin "26") (pinfunction "IO14_26") (pintype "bidirectional+no_connect"))
    )
    (net (code "89") (name "unconnected-(J5-IO15-Pad3)") (class "Default")
      (node (ref "J5") (pin "3") (pinfunction "IO15_3") (pintype "bidirectional+no_connect"))
    )
    (net (code "90") (name "unconnected-(J5-IO18-Pad9)") (class "Default")
      (node (ref "J5") (pin "9") (pinfunction "IO18_9") (pintype "bidirectional+no_connect"))
    )
    (net (code "91") (name "unconnected-(J5-IO19-Pad10)") (class "Default")
      (node (ref "J5") (pin "10") (pinfunction "IO19_10") (pintype "bidirectional+no_connect"))
    )
    (net (code "92") (name "unconnected-(J5-IO21-Pad11)") (class "Default")
      (node (ref "J5") (pin "11") (pinfunction "IO21_11") (pintype "bidirectional+no_connect"))
    )
    (net (code "93") (name "unconnected-(J5-IO22-Pad14)") (class "Default")
      (node (ref "J5") (pin "14") (pinfunction "IO22_14") (pintype "bidirectional+no_connect"))
    )
    (net (code "94") (name "unconnected-(J5-IO23-Pad15)") (class "Default")
      (node (ref "J5") (pin "15") (pinfunction "IO23_15") (pintype "bidirectional+no_connect"))
    )
    (net (code "95") (name "unconnected-(J5-IO25-Pad23)") (class "Default")
      (node (ref "J5") (pin "23") (pinfunction "IO25_23") (pintype "bidirectional+no_connect"))
    )
    (net (code "96") (name "unconnected-(J5-IO26-Pad24)") (class "Default")
      (node (ref "J5") (pin "24") (pinfunction "IO26_24") (pintype "bidirectional+no_connect"))
    )
    (net (code "97") (name "unconnected-(J5-IO27-Pad25)") (class "Default")
      (node (ref "J5") (pin "25") (pinfunction "IO27_25") (pintype "bidirectional+no_connect"))
    )
    (net (code "98") (name "unconnected-(J5-IO32-Pad21)") (class "Default")
      (node (ref "J5") (pin "21") (pinfunction "IO32_21") (pintype "bidirectional+no_connect"))
    )
    (net (code "99") (name "unconnected-(J5-IO33-Pad22)") (class "Default")
      (node (ref "J5") (pin "22") (pinfunction "IO33_22") (pintype "bidirectional+no_connect"))
    )
    (net (code "100") (name "unconnected-(J5-IO34-Pad19)") (class "Default")
      (node (ref "J5") (pin "19") (pinfunction "IO34_19") (pintype "bidirectional+no_connect"))
    )
    (net (code "101") (name "unconnected-(J5-IO35-Pad20)") (class "Default")
      (node (ref "J5") (pin "20") (pinfunction "IO35_20") (pintype "bidirectional+no_connect"))
    )
    (net (code "102") (name "unconnected-(J5-VN-Pad18)") (class "Default")
      (node (ref "J5") (pin "18") (pinfunction "VN_18") (pintype "bidirectional+no_connect"))
    )
    (net (code "103") (name "unconnected-(J5-VP-Pad17)") (class "Default")
      (node (ref "J5") (pin "17") (pinfunction "VP_17") (pintype "bidirectional+no_connect"))
    )
    (net (code "104") (name "unconnected-(K3A-NC-Pad2)") (class "Default")
      (node (ref "K3") (pin "2") (pinfunction "NC_2") (pintype "passive+no_connect"))
    )
    (net (code "105") (name "unconnected-(K4A-NC-Pad2)") (class "Default")
      (node (ref "K4") (pin "2") (pinfunction "NC_2") (pintype "passive+no_connect"))
    )
    (net (code "106") (name "unconnected-(K5A-NC-Pad2)") (class "Default")
      (node (ref "K5") (pin "2") (pinfunction "NC_2") (pintype "passive+no_connect"))
    )
    (net (code "107") (name "unconnected-(K6A-NC-Pad2)") (class "Default")
      (node (ref "K6") (pin "2") (pinfunction "NC_2") (pintype "passive+no_connect"))
    )
    (net (code "108") (name "unconnected-(K8A-NC-Pad2)") (class "Default")
      (node (ref "K8") (pin "2") (pinfunction "NC_2") (pintype "passive+no_connect"))
    )
    (net (code "109") (name "unconnected-(U1-PA1-Pad7)") (class "Default")
      (node (ref "U1") (pin "7") (pinfunction "PA1_7") (pintype "bidirectional+no_connect"))
    )
    (net (code "110") (name "unconnected-(U1-PB1-Pad5)") (class "Default")
      (node (ref "U1") (pin "5") (pinfunction "PB1_5") (pintype "bidirectional+no_connect"))
    )
    (net (code "111") (name "unconnected-(U1-PW1-Pad6)") (class "Default")
      (node (ref "U1") (pin "6") (pinfunction "PW1_6") (pintype "bidirectional+no_connect"))
    )
  )
)
